# Power.net
KiCad netlist of a schematic drawn in Altium Designer
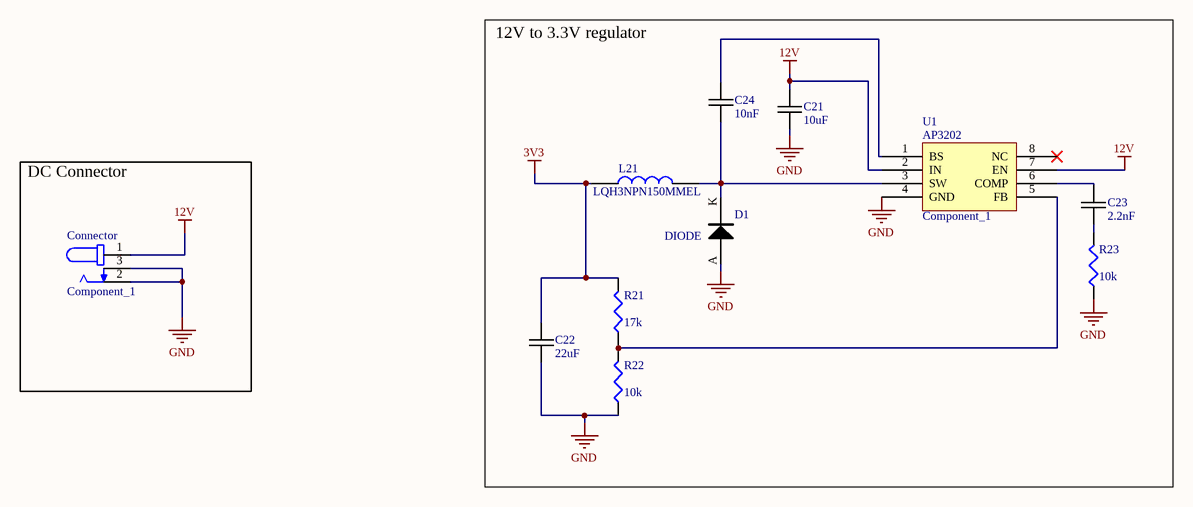
[diagram p0: Power.SchDoc]

(export (version "E")
  (design (tool "Eeschema 10.0.6"))
  (components
    (comp (ref "C21")
      (value "10uF")
      (footprint "0603C-GENERIC")
      (description "GENERIC CAPACITOR NON POLARISED 0603")
      (libsource (lib "vh_altium_library") (part "C0603-GENERIC"))
    )
    (comp (ref "C22")
      (value "22uF")
      (footprint "0603C-GENERIC")
      (description "GENERIC CAPACITOR NON POLARISED 0603")
      (libsource (lib "vh_altium_library") (part "C0603-GENERIC"))
    )
    (comp (ref "C23")
      (value "2.2nF")
      (footprint "0603C-GENERIC")
      (description "GENERIC CAPACITOR NON POLARISED 0603")
      (libsource (lib "vh_altium_library") (part "C0603-GENERIC"))
    )
    (comp (ref "C24")
      (value "10nF")
      (footprint "0603C-GENERIC")
      (description "GENERIC CAPACITOR NON POLARISED 0603")
      (libsource (lib "vh_altium_library") (part "C0603-GENERIC"))
    )
    (comp (ref "Connector")
      (value "Component_1")
      (footprint "PCBComponent_1")
      (libsource (lib "ConectorDC2.0") (part "Component_1"))
    )
    (comp (ref "D1")
      (value "DIODE")
      (footprint "RESC2012X65N:RESC2012X65N")
      (description "GENERIC DIODE")
      (libsource (lib "vh_altium_library") (part "DIODE-GENERIC"))
    )
    (comp (ref "L21")
      (value "LQH3NPN150MMEL")
      (footprint "IND_LQH3NPH3R3MMEL")
      (description "Inductor with Inductance 3.3uH Tol.+/-20% Package 1212 (3030)")
      (fields
        (field (name "DIGI-KEY_PART_NUMBER") "490-LQH3NPH3R3MMELCT-ND")
        (field (name "MP") "LQH3NPH3R3MMEL")
      )
      (libsource (lib "LQH3NPH3R3MMEL") (part "LQH3NPH3R3MMEL"))
    )
    (comp (ref "R21")
      (value "17k")
      (footprint "J1-0603")
      (description "Resistor")
      (fields (field (name "PUBLISHER") "Altium Limited"))
      (libsource (lib "Miscellaneous Devices") (part "Res3"))
    )
    (comp (ref "R22")
      (value "10k")
      (footprint "J1-0603")
      (description "Resistor")
      (fields (field (name "PUBLISHER") "Altium Limited"))
      (libsource (lib "Miscellaneous Devices") (part "Res3"))
    )
    (comp (ref "R23")
      (value "10k")
      (footprint "J1-0603")
      (description "Resistor")
      (fields (field (name "PUBLISHER") "Altium Limited"))
      (libsource (lib "Miscellaneous Devices") (part "Res3"))
    )
    (comp (ref "U1")
      (value "Component_1")
      (footprint "AP3202")
      (libsource (lib "LSEL_Library") (part "Component_1"))
    )
  )
  (nets
    (net (code "1") (name "3V3") (class "Default")
      (node (ref "C22") (pin "1") (pintype "passive"))
      (node (ref "L21") (pin "1") (pinfunction "1_1") (pintype "passive"))
      (node (ref "R21") (pin "2") (pinfunction "2_2") (pintype "passive"))
    )
    (net (code "2") (name "12V") (class "Default")
      (node (ref "C21") (pin "1") (pintype "passive"))
      (node (ref "Connector") (pin "1") (pinfunction "1_1") (pintype "passive"))
      (node (ref "U1") (pin "2") (pinfunction "IN_2") (pintype "passive"))
      (node (ref "U1") (pin "7") (pinfunction "EN_7") (pintype "passive"))
    )
    (net (code "3") (name "GND") (class "Default")
      (node (ref "C21") (pin "2") (pintype "passive"))
      (node (ref "C22") (pin "2") (pintype "passive"))
      (node (ref "Connector") (pin "2") (pinfunction "2_2") (pintype "passive"))
      (node (ref "Connector") (pin "3") (pinfunction "3_3") (pintype "passive"))
      (node (ref "D1") (pin "A") (pinfunction "A_A") (pintype "passive"))
      (node (ref "R22") (pin "1") (pinfunction "1_1") (pintype "passive"))
      (node (ref "R23") (pin "1") (pinfunction "1_1") (pintype "passive"))
      (node (ref "U1") (pin "4") (pinfunction "GND_4") (pintype "passive"))
    )
    (net (code "4") (name "Net-(C23-Pad2)") (class "Default")
      (node (ref "C23") (pin "2") (pintype "passive"))
      (node (ref "R23") (pin "2") (pinfunction "2_2") (pintype "passive"))
    )
    (net (code "5") (name "Net-(U1-BS)") (class "Default")
      (node (ref "C24") (pin "1") (pintype "passive"))
      (node (ref "U1") (pin "1") (pinfunction "BS_1") (pintype "passive"))
    )
    (net (code "6") (name "Net-(U1-COMP)") (class "Default")
      (node (ref "C23") (pin "1") (pintype "passive"))
      (node (ref "U1") (pin "6") (pinfunction "COMP_6") (pintype "passive"))
    )
    (net (code "7") (name "Net-(U1-FB)") (class "Default")
      (node (ref "R21") (pin "1") (pinfunction "1_1") (pintype "passive"))
      (node (ref "R22") (pin "2") (pinfunction "2_2") (pintype "passive"))
      (node (ref "U1") (pin "5") (pinfunction "FB_5") (pintype "passive"))
    )
    (net (code "8") (name "Net-(U1-SW)") (class "Default")
      (node (ref "C24") (pin "2") (pintype "passive"))
      (node (ref "D1") (pin "K") (pinfunction "K_K") (pintype "passive"))
      (node (ref "L21") (pin "2") (pinfunction "2_2") (pintype "passive"))
      (node (ref "U1") (pin "3") (pinfunction "SW_3") (pintype "passive"))
    )
    (net (code "9") (name "unconnected-(U1-NC-Pad8)") (class "Default")
      (node (ref "U1") (pin "8") (pinfunction "NC_8") (pintype "passive+no_connect"))
    )
  )
)
